# CH32V307WCU6-R0.net
KiCad netlist of a schematic drawn in Altium Designer
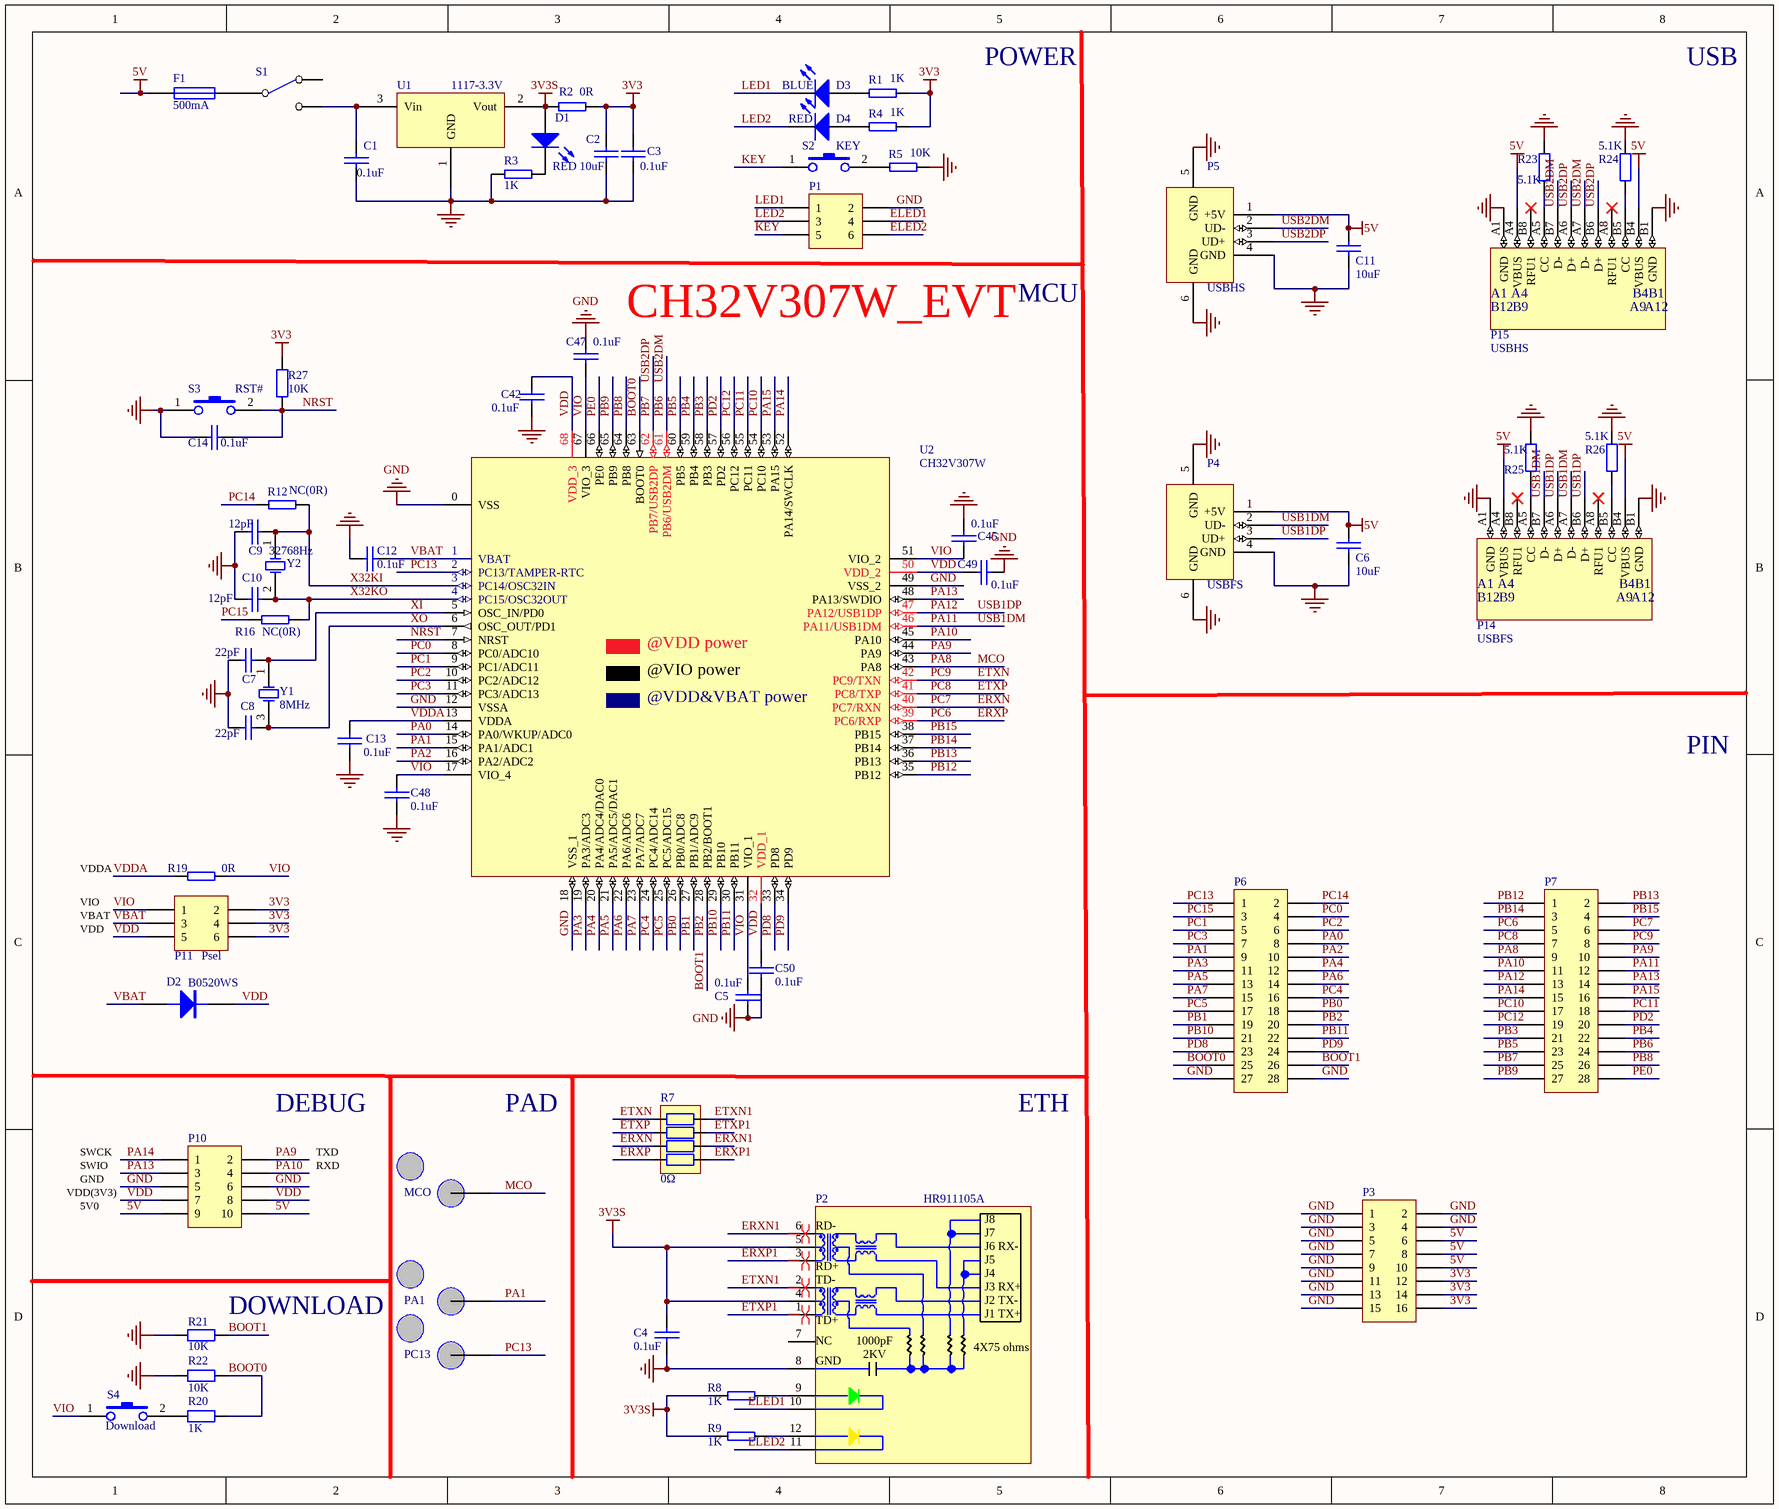
[diagram p0: CH32V307WCU6-R0.SchDoc]

(export (version "E")
  (design (tool "Eeschema 10.0.6"))
  (components
    (comp (ref "C1")
      (value "0.1uF")
      (footprint "0603_C")
      (description "Capacitor")
      (libsource (lib "*") (part "CAP"))
    )
    (comp (ref "C2")
      (value "10uF")
      (footprint "3216_C")
      (description "Capacitor")
      (libsource (lib "*") (part "CAP"))
    )
    (comp (ref "C3")
      (value "0.1uF")
      (footprint "0603_C")
      (description "Capacitor")
      (libsource (lib "*") (part "CAP"))
    )
    (comp (ref "C4")
      (value "0.1uF")
      (footprint "0603_C")
      (description "Capacitor")
      (libsource (lib "*") (part "CAP"))
    )
    (comp (ref "C5")
      (value "0.1uF")
      (footprint "0603_C")
      (description "Capacitor")
      (libsource (lib "*") (part "CAP"))
    )
    (comp (ref "C6")
      (value "10uF")
      (footprint "3216_C")
      (description "Capacitor")
      (libsource (lib "") (part "CAP_1"))
    )
    (comp (ref "C7")
      (value "22pF")
      (footprint "0603_C")
      (description "Capacitor")
      (libsource (lib "*") (part "CAP"))
    )
    (comp (ref "C8")
      (value "22pF")
      (footprint "0603_C")
      (description "Capacitor")
      (libsource (lib "*") (part "CAP"))
    )
    (comp (ref "C9")
      (value "12pF")
      (footprint "0603_C")
      (description "Capacitor")
      (libsource (lib "*") (part "CAP"))
    )
    (comp (ref "C10")
      (value "12pF")
      (footprint "0603_C")
      (description "Capacitor")
      (libsource (lib "*") (part "CAP"))
    )
    (comp (ref "C11")
      (value "10uF")
      (footprint "3216_C")
      (description "Capacitor")
      (libsource (lib "") (part "CAP_1"))
    )
    (comp (ref "C12")
      (value "0.1uF")
      (footprint "0603_C")
      (description "Capacitor")
      (libsource (lib "*") (part "CAP"))
    )
    (comp (ref "C13")
      (value "0.1uF")
      (footprint "0603_C")
      (description "Capacitor")
      (libsource (lib "*") (part "CAP"))
    )
    (comp (ref "C14")
      (value "0.1uF")
      (footprint "0603_C")
      (description "Capacitor")
      (libsource (lib "") (part "CAP_1"))
    )
    (comp (ref "C42")
      (value "0.1uF")
      (footprint "0603_C")
      (description "Capacitor")
      (libsource (lib "*") (part "CAP"))
    )
    (comp (ref "C45")
      (value "0.1uF")
      (footprint "0603_C")
      (description "Capacitor")
      (libsource (lib "*") (part "CAP"))
    )
    (comp (ref "C47")
      (value "0.1uF")
      (footprint "0603_C")
      (description "Capacitor")
      (libsource (lib "*") (part "CAP"))
    )
    (comp (ref "C48")
      (value "0.1uF")
      (footprint "0603_C")
      (description "Capacitor")
      (libsource (lib "*") (part "CAP"))
    )
    (comp (ref "C49")
      (value "0.1uF")
      (footprint "0603_C")
      (description "Capacitor")
      (libsource (lib "*") (part "CAP"))
    )
    (comp (ref "C50")
      (value "0.1uF")
      (footprint "0603_C")
      (description "Capacitor")
      (libsource (lib "*") (part "CAP"))
    )
    (comp (ref "D1")
      (value "RED")
      (footprint "0603+")
      (description "Typical INFRARED GaAs LED")
      (fields (field (name "PUBLISHER") "Altium Limited"))
      (libsource (lib "*") (part "LED0"))
    )
    (comp (ref "D2")
      (value "B0520WS")
      (footprint "SOD-323")
      (description "Diode")
      (libsource (lib "*") (part "DIODE"))
    )
    (comp (ref "D3")
      (value "BLUE")
      (footprint "0603+")
      (description "Typical INFRARED GaAs LED")
      (fields (field (name "PUBLISHER") "Altium Limited"))
      (libsource (lib "*") (part "LED0"))
    )
    (comp (ref "D4")
      (value "RED")
      (footprint "0603+")
      (description "Typical INFRARED GaAs LED")
      (fields (field (name "PUBLISHER") "Altium Limited"))
      (libsource (lib "*") (part "LED0"))
    )
    (comp (ref "F1")
      (value "500mA")
      (footprint "0603")
      (description "Fuse")
      (libsource (lib "wch_sch_others") (part "FUSE1"))
    )
    (comp (ref "MCO")
      (value "Testpoint")
      (footprint "TESTPOINT1")
      (description "测试点")
      (libsource (lib "wch_sch_others") (part "Testpoint"))
    )
    (comp (ref "P1")
      (value "IO")
      (footprint "IDC6-2.54mm")
      (description "Header, 3-Pin, Dual row, Right Angle")
      (fields (field (name "PUBLISHER") "Altium Limited"))
      (libsource (lib "Miscellaneous Connectors") (part "Header 3X2H"))
    )
    (comp (ref "P2") (value "HR911105A") (footprint "HR911105A") (libsource (lib "*") (part "HR911105A")))
    (comp (ref "P3")
      (value "Ppin")
      (footprint "IDC16-2.54mm")
      (description "Header, 8-Pin, Dual row, Right Angle")
      (fields (field (name "PUBLISHER") "Altium Limited"))
      (libsource (lib "Miscellaneous Connectors") (part "Header 8X2H"))
    )
    (comp (ref "P4")
      (value "USBFS")
      (footprint "USBAF")
      (description "USB Port")
      (libsource (lib "*") (part "USB"))
    )
    (comp (ref "P5")
      (value "USBHS")
      (footprint "USBAF")
      (description "USB Port")
      (libsource (lib "*") (part "USB"))
    )
    (comp (ref "P6")
      (value "HEADER 14x2")
      (footprint "MYPCB:IDC28-2.54MM")
      (description "Header, 14-Pin, Dual row")
      (libsource (lib "wch_sch_others") (part "HEADER 14x2"))
    )
    (comp (ref "P7")
      (value "HEADER 14x2")
      (footprint "MYPCB:IDC28-2.54MM")
      (description "Header, 14-Pin, Dual row")
      (libsource (lib "wch_sch_others") (part "HEADER 14x2"))
    )
    (comp (ref "P10")
      (value "LINK")
      (footprint "IDC10-2.54mm")
      (description "Header, 5-Pin, Dual row, Right Angle")
      (fields (field (name "PUBLISHER") "Altium Limited"))
      (libsource (lib "Miscellaneous Connectors") (part "Header 5X2H"))
    )
    (comp (ref "P11")
      (value "Psel")
      (footprint "IDC6-2.54mm")
      (description "Header, 3-Pin, Dual row, Right Angle")
      (fields (field (name "PUBLISHER") "Altium Limited"))
      (libsource (lib "Miscellaneous Connectors") (part "Header 3X2H"))
    )
    (comp (ref "P14")
      (value "USBFS")
      (footprint "TYPE-C-Receptacle-2.0")
      (libsource (lib "*") (part "TYPE-C1"))
    )
    (comp (ref "P15")
      (value "USBHS")
      (footprint "TYPE-C-Receptacle-2.0")
      (libsource (lib "*") (part "TYPE-C1"))
    )
    (comp (ref "PA1")
      (value "Testpoint")
      (footprint "TESTPOINT1")
      (description "测试点")
      (libsource (lib "wch_sch_others") (part "Testpoint"))
    )
    (comp (ref "PC13")
      (value "Testpoint")
      (footprint "TESTPOINT1")
      (description "测试点")
      (libsource (lib "wch_sch_others") (part "Testpoint"))
    )
    (comp (ref "R1") (value "1K") (footprint "0603") (libsource (lib "wch_sch_others") (part "RES")))
    (comp (ref "R2") (value "0R") (footprint "0603") (libsource (lib "wch_sch_others") (part "RES")))
    (comp (ref "R3") (value "1K") (footprint "0603") (libsource (lib "wch_sch_others") (part "RES")))
    (comp (ref "R4") (value "1K") (footprint "0603") (libsource (lib "wch_sch_others") (part "RES")))
    (comp (ref "R5") (value "10K") (footprint "0603") (libsource (lib "wch_sch_others") (part "RES")))
    (comp (ref "R7")
      (value "0Ω")
      (footprint "8P4R-0603")
      (description "贴片网络排阻")
      (fields (field (name "版权归属") "源创客"))
      (libsource (lib "wch_sch_others") (part "R-8P4R"))
    )
    (comp (ref "R8") (value "1K") (footprint "0603") (libsource (lib "wch_sch_others") (part "RES")))
    (comp (ref "R9") (value "1K") (footprint "0603") (libsource (lib "wch_sch_others") (part "RES")))
    (comp (ref "R12") (value "NC(0R)") (footprint "0603") (libsource (lib "wch_sch_others") (part "RES")))
    (comp (ref "R16") (value "NC(0R)") (footprint "0603") (libsource (lib "wch_sch_others") (part "RES")))
    (comp (ref "R19") (value "0R") (footprint "0603") (libsource (lib "*") (part "R")))
    (comp (ref "R20")
      (value "1K")
      (footprint "0603")
      (description "Resistor")
      (fields (field (name "PUBLISHER") "Altium Limited"))
      (libsource (lib "") (part "Res2_1"))
    )
    (comp (ref "R21")
      (value "10K")
      (footprint "0603")
      (description "Resistor")
      (fields (field (name "PUBLISHER") "Altium Limited"))
      (libsource (lib "") (part "Res2_1"))
    )
    (comp (ref "R22")
      (value "10K")
      (footprint "0603")
      (description "Resistor")
      (fields (field (name "PUBLISHER") "Altium Limited"))
      (libsource (lib "") (part "Res2_1"))
    )
    (comp (ref "R23")
      (value "5.1K")
      (footprint "0603")
      (description "Resistor")
      (libsource (lib "Miscellaneous Devices") (part "Res2"))
    )
    (comp (ref "R24")
      (value "5.1K")
      (footprint "0603")
      (description "Resistor")
      (libsource (lib "Miscellaneous Devices") (part "Res2"))
    )
    (comp (ref "R25")
      (value "5.1K")
      (footprint "0603")
      (description "Resistor")
      (libsource (lib "Miscellaneous Devices") (part "Res2"))
    )
    (comp (ref "R26")
      (value "5.1K")
      (footprint "0603")
      (description "Resistor")
      (libsource (lib "Miscellaneous Devices") (part "Res2"))
    )
    (comp (ref "R27")
      (value "10K")
      (footprint "0603")
      (description "Resistor")
      (fields (field (name "PUBLISHER") "Altium Limited"))
      (libsource (lib "Miscellaneous Devices") (part "Res2"))
    )
    (comp (ref "S1") (value "SW SPDT") (footprint "KEY2") (libsource (lib "*") (part "SW SPDT")))
    (comp (ref "S2")
      (value "KEY")
      (footprint "SMD_6.1x3.65x2.5mm-KEY")
      (libsource (lib "wch_sch_others") (part "KEY1"))
    )
    (comp (ref "S3")
      (value "RST#")
      (footprint "SMD_6.1x3.65x2.5mm-KEY")
      (libsource (lib "wch_sch_others") (part "KEY1"))
    )
    (comp (ref "S4")
      (value "Download")
      (footprint "SMD_6.1x3.65x2.5mm-KEY")
      (libsource (lib "wch_sch_others") (part "KEY1"))
    )
    (comp (ref "U1")
      (value "1117-3.3V")
      (footprint "SOT-223")
      (libsource (lib "wch_sch_others") (part "1117-3.3V"))
    )
    (comp (ref "U2")
      (value "CH32V307W")
      (footprint "QFN68_8x8")
      (description "RISC-V FPU HD-MCU, 144MHz, USB_480M, USB OTG, 1000M Ethernet MAC, 2*CAN")
      (libsource (lib "CHXXX") (part "CH32V307W"))
    )
    (comp (ref "Y1")
      (value "8MHz")
      (footprint "XT3225")
      (description "Crystal Oscillator")
      (fields (field (name "PUBLISHER") "Altium Limited"))
      (libsource (lib "") (part "XTAL_1"))
    )
    (comp (ref "Y2")
      (value "32768Hz")
      (footprint "FC-135")
      (description "Crystal Oscillator")
      (fields (field (name "PUBLISHER") "Altium Limited"))
      (libsource (lib "*") (part "XTAL"))
    )
  )
  (nets
    (net (code "2") (name "/BOOT0") (class "Default")
      (node (ref "P6") (pin "25") (pinfunction "25_25") (pintype "passive"))
      (node (ref "R20") (pin "1") (pinfunction "1_1") (pintype "passive"))
      (node (ref "R22") (pin "1") (pinfunction "1_1") (pintype "passive"))
      (node (ref "U2") (pin "63") (pinfunction "BOOT0_63") (pintype "input"))
    )
    (net (code "3") (name "/BOOT1") (class "Default")
      (node (ref "P6") (pin "20") (pinfunction "20_20") (pintype "passive"))
      (node (ref "P6") (pin "26") (pinfunction "26_26") (pintype "passive"))
      (node (ref "R21") (pin "1") (pinfunction "1_1") (pintype "passive"))
      (node (ref "U2") (pin "28") (pinfunction "PB2/BOOT1_28") (pintype "bidirectional"))
    )
    (net (code "4") (name "/ELED1") (class "Default")
      (node (ref "P1") (pin "4") (pinfunction "4_4") (pintype "passive"))
      (node (ref "P2") (pin "10") (pintype "passive"))
    )
    (net (code "5") (name "/ELED2") (class "Default")
      (node (ref "P1") (pin "6") (pinfunction "6_6") (pintype "passive"))
      (node (ref "P2") (pin "11") (pintype "passive"))
    )
    (net (code "6") (name "/ERXN") (class "Default")
      (node (ref "P7") (pin "6") (pinfunction "6_6") (pintype "passive"))
      (node (ref "R7") (pin "3") (pinfunction "3_3") (pintype "passive"))
      (node (ref "U2") (pin "40") (pinfunction "PC7/RXN_40") (pintype "bidirectional"))
    )
    (net (code "7") (name "/ERXN1") (class "Default")
      (node (ref "P2") (pin "6") (pintype "passive"))
      (node (ref "R7") (pin "6") (pinfunction "6_6") (pintype "passive"))
    )
    (net (code "8") (name "/ERXP") (class "Default")
      (node (ref "P7") (pin "5") (pinfunction "5_5") (pintype "passive"))
      (node (ref "R7") (pin "4") (pinfunction "4_4") (pintype "passive"))
      (node (ref "U2") (pin "39") (pinfunction "PC6/RXP_39") (pintype "bidirectional"))
    )
    (net (code "9") (name "/ERXP1") (class "Default")
      (node (ref "P2") (pin "3") (pintype "passive"))
      (node (ref "R7") (pin "5") (pinfunction "5_5") (pintype "passive"))
    )
    (net (code "10") (name "/ETXN") (class "Default")
      (node (ref "P7") (pin "8") (pinfunction "8_8") (pintype "passive"))
      (node (ref "R7") (pin "1") (pinfunction "1_1") (pintype "passive"))
      (node (ref "U2") (pin "42") (pinfunction "PC9/TXN_42") (pintype "bidirectional"))
    )
    (net (code "11") (name "/ETXN1") (class "Default")
      (node (ref "P2") (pin "2") (pintype "passive"))
      (node (ref "R7") (pin "8") (pinfunction "8_8") (pintype "passive"))
    )
    (net (code "12") (name "/ETXP") (class "Default")
      (node (ref "P7") (pin "7") (pinfunction "7_7") (pintype "passive"))
      (node (ref "R7") (pin "2") (pinfunction "2_2") (pintype "passive"))
      (node (ref "U2") (pin "41") (pinfunction "PC8/TXP_41") (pintype "bidirectional"))
    )
    (net (code "13") (name "/ETXP1") (class "Default")
      (node (ref "P2") (pin "1") (pintype "passive"))
      (node (ref "R7") (pin "7") (pinfunction "7_7") (pintype "passive"))
    )
    (net (code "14") (name "/KEY") (class "Default")
      (node (ref "P1") (pin "5") (pinfunction "5_5") (pintype "passive"))
      (node (ref "S2") (pin "1") (pinfunction "1_1") (pintype "passive"))
    )
    (net (code "15") (name "/LED1") (class "Default")
      (node (ref "D3") (pin "2") (pinfunction "K_2") (pintype "passive"))
      (node (ref "P1") (pin "1") (pinfunction "1_1") (pintype "passive"))
    )
    (net (code "16") (name "/LED2") (class "Default")
      (node (ref "D4") (pin "2") (pinfunction "K_2") (pintype "passive"))
      (node (ref "P1") (pin "3") (pinfunction "3_3") (pintype "passive"))
    )
    (net (code "17") (name "/MCO") (class "Default")
      (node (ref "MCO") (pin "1") (pinfunction "point_1") (pintype "passive"))
      (node (ref "P7") (pin "9") (pinfunction "9_9") (pintype "passive"))
      (node (ref "U2") (pin "43") (pinfunction "PA8_43") (pintype "bidirectional"))
    )
    (net (code "18") (name "/NRST") (class "Default")
      (node (ref "C14") (pin "2") (pinfunction "2_2") (pintype "passive"))
      (node (ref "R27") (pin "1") (pinfunction "1_1") (pintype "passive"))
      (node (ref "S3") (pin "2") (pinfunction "2_2") (pintype "passive"))
      (node (ref "U2") (pin "7") (pinfunction "NRST_7") (pintype "input"))
    )
    (net (code "19") (name "/PA0") (class "Default")
      (node (ref "P6") (pin "8") (pinfunction "8_8") (pintype "passive"))
      (node (ref "U2") (pin "14") (pinfunction "PA0/WKUP/ADC0_14") (pintype "bidirectional"))
    )
    (net (code "20") (name "/PA1") (class "Default")
      (node (ref "P6") (pin "9") (pinfunction "9_9") (pintype "passive"))
      (node (ref "PA1") (pin "1") (pinfunction "point_1") (pintype "passive"))
      (node (ref "U2") (pin "15") (pinfunction "PA1/ADC1_15") (pintype "bidirectional"))
    )
    (net (code "21") (name "/PA2") (class "Default")
      (node (ref "P6") (pin "10") (pinfunction "10_10") (pintype "passive"))
      (node (ref "U2") (pin "16") (pinfunction "PA2/ADC2_16") (pintype "bidirectional"))
    )
    (net (code "22") (name "/PA3") (class "Default")
      (node (ref "P6") (pin "11") (pinfunction "11_11") (pintype "passive"))
      (node (ref "U2") (pin "19") (pinfunction "PA3/ADC3_19") (pintype "bidirectional"))
    )
    (net (code "23") (name "/PA4") (class "Default")
      (node (ref "P6") (pin "12") (pinfunction "12_12") (pintype "passive"))
      (node (ref "U2") (pin "20") (pinfunction "PA4/ADC4/DAC0_20") (pintype "bidirectional"))
    )
    (net (code "24") (name "/PA5") (class "Default")
      (node (ref "P6") (pin "13") (pinfunction "13_13") (pintype "passive"))
      (node (ref "U2") (pin "21") (pinfunction "PA5/ADC5/DAC1_21") (pintype "bidirectional"))
    )
    (net (code "25") (name "/PA6") (class "Default")
      (node (ref "P6") (pin "14") (pinfunction "14_14") (pintype "passive"))
      (node (ref "U2") (pin "22") (pinfunction "PA6/ADC6_22") (pintype "bidirectional"))
    )
    (net (code "26") (name "/PA7") (class "Default")
      (node (ref "P6") (pin "15") (pinfunction "15_15") (pintype "passive"))
      (node (ref "U2") (pin "23") (pinfunction "PA7/ADC7_23") (pintype "bidirectional"))
    )
    (net (code "27") (name "/PA9") (class "Default")
      (node (ref "P10") (pin "2") (pinfunction "2_2") (pintype "passive"))
      (node (ref "P7") (pin "10") (pinfunction "10_10") (pintype "passive"))
      (node (ref "U2") (pin "44") (pinfunction "PA9_44") (pintype "bidirectional"))
    )
    (net (code "28") (name "/PA10") (class "Default")
      (node (ref "P10") (pin "4") (pinfunction "4_4") (pintype "passive"))
      (node (ref "P7") (pin "11") (pinfunction "11_11") (pintype "passive"))
      (node (ref "U2") (pin "45") (pinfunction "PA10_45") (pintype "bidirectional"))
    )
    (net (code "29") (name "/PA11") (class "Default")
      (node (ref "P14") (pin "A7") (pinfunction "D-_A7") (pintype "bidirectional"))
      (node (ref "P14") (pin "B7") (pinfunction "D-_B7") (pintype "bidirectional"))
      (node (ref "P4") (pin "2") (pinfunction "UD-_2") (pintype "bidirectional"))
      (node (ref "P7") (pin "12") (pinfunction "12_12") (pintype "passive"))
      (node (ref "U2") (pin "46") (pinfunction "PA11/USB1DM_46") (pintype "bidirectional"))
    )
    (net (code "30") (name "/PA12") (class "Default")
      (node (ref "P14") (pin "A6") (pinfunction "D+_A6") (pintype "bidirectional"))
      (node (ref "P14") (pin "B6") (pinfunction "D+_B6") (pintype "bidirectional"))
      (node (ref "P4") (pin "3") (pinfunction "UD+_3") (pintype "bidirectional"))
      (node (ref "P7") (pin "13") (pinfunction "13_13") (pintype "passive"))
      (node (ref "U2") (pin "47") (pinfunction "PA12/USB1DP_47") (pintype "bidirectional"))
    )
    (net (code "31") (name "/PA13") (class "Default")
      (node (ref "P10") (pin "3") (pinfunction "3_3") (pintype "passive"))
      (node (ref "P7") (pin "14") (pinfunction "14_14") (pintype "passive"))
      (node (ref "U2") (pin "48") (pinfunction "PA13/SWDIO_48") (pintype "bidirectional"))
    )
    (net (code "32") (name "/PA14") (class "Default")
      (node (ref "P10") (pin "1") (pinfunction "1_1") (pintype "passive"))
      (node (ref "P7") (pin "15") (pinfunction "15_15") (pintype "passive"))
      (node (ref "U2") (pin "52") (pinfunction "PA14/SWCLK_52") (pintype "bidirectional"))
    )
    (net (code "33") (name "/PA15") (class "Default")
      (node (ref "P7") (pin "16") (pinfunction "16_16") (pintype "passive"))
      (node (ref "U2") (pin "53") (pinfunction "PA15_53") (pintype "bidirectional"))
    )
    (net (code "34") (name "/PB0") (class "Default")
      (node (ref "P6") (pin "18") (pinfunction "18_18") (pintype "passive"))
      (node (ref "U2") (pin "26") (pinfunction "PB0/ADC8_26") (pintype "bidirectional"))
    )
    (net (code "35") (name "/PB1") (class "Default")
      (node (ref "P6") (pin "19") (pinfunction "19_19") (pintype "passive"))
      (node (ref "U2") (pin "27") (pinfunction "PB1/ADC9_27") (pintype "bidirectional"))
    )
    (net (code "36") (name "/PB3") (class "Default")
      (node (ref "P7") (pin "21") (pinfunction "21_21") (pintype "passive"))
      (node (ref "U2") (pin "58") (pinfunction "PB3_58") (pintype "bidirectional"))
    )
    (net (code "37") (name "/PB4") (class "Default")
      (node (ref "P7") (pin "22") (pinfunction "22_22") (pintype "passive"))
      (node (ref "U2") (pin "59") (pinfunction "PB4_59") (pintype "bidirectional"))
    )
    (net (code "38") (name "/PB5") (class "Default")
      (node (ref "P7") (pin "23") (pinfunction "23_23") (pintype "passive"))
      (node (ref "U2") (pin "60") (pinfunction "PB5_60") (pintype "bidirectional"))
    )
    (net (code "39") (name "/PB6") (class "Default")
      (node (ref "P15") (pin "A7") (pinfunction "D-_A7") (pintype "bidirectional"))
      (node (ref "P15") (pin "B7") (pinfunction "D-_B7") (pintype "bidirectional"))
      (node (ref "P5") (pin "2") (pinfunction "UD-_2") (pintype "bidirectional"))
      (node (ref "P7") (pin "24") (pinfunction "24_24") (pintype "passive"))
      (node (ref "U2") (pin "61") (pinfunction "PB6/USB2DM_61") (pintype "bidirectional"))
    )
    (net (code "40") (name "/PB7") (class "Default")
      (node (ref "P15") (pin "A6") (pinfunction "D+_A6") (pintype "bidirectional"))
      (node (ref "P15") (pin "B6") (pinfunction "D+_B6") (pintype "bidirectional"))
      (node (ref "P5") (pin "3") (pinfunction "UD+_3") (pintype "bidirectional"))
      (node (ref "P7") (pin "25") (pinfunction "25_25") (pintype "passive"))
      (node (ref "U2") (pin "62") (pinfunction "PB7/USB2DP_62") (pintype "bidirectional"))
    )
    (net (code "41") (name "/PB8") (class "Default")
      (node (ref "P7") (pin "26") (pinfunction "26_26") (pintype "passive"))
      (node (ref "U2") (pin "64") (pinfunction "PB8_64") (pintype "bidirectional"))
    )
    (net (code "42") (name "/PB9") (class "Default")
      (node (ref "P7") (pin "27") (pinfunction "27_27") (pintype "passive"))
      (node (ref "U2") (pin "65") (pinfunction "PB9_65") (pintype "bidirectional"))
    )
    (net (code "43") (name "/PB10") (class "Default")
      (node (ref "P6") (pin "21") (pinfunction "21_21") (pintype "passive"))
      (node (ref "U2") (pin "29") (pinfunction "PB10_29") (pintype "bidirectional"))
    )
    (net (code "44") (name "/PB11") (class "Default")
      (node (ref "P6") (pin "22") (pinfunction "22_22") (pintype "passive"))
      (node (ref "U2") (pin "30") (pinfunction "PB11_30") (pintype "bidirectional"))
    )
    (net (code "45") (name "/PB12") (class "Default")
      (node (ref "P7") (pin "1") (pinfunction "1_1") (pintype "passive"))
      (node (ref "U2") (pin "35") (pinfunction "PB12_35") (pintype "bidirectional"))
    )
    (net (code "46") (name "/PB13") (class "Default")
      (node (ref "P7") (pin "2") (pinfunction "2_2") (pintype "passive"))
      (node (ref "U2") (pin "36") (pinfunction "PB13_36") (pintype "bidirectional"))
    )
    (net (code "47") (name "/PB14") (class "Default")
      (node (ref "P7") (pin "3") (pinfunction "3_3") (pintype "passive"))
      (node (ref "U2") (pin "37") (pinfunction "PB14_37") (pintype "bidirectional"))
    )
    (net (code "48") (name "/PB15") (class "Default")
      (node (ref "P7") (pin "4") (pinfunction "4_4") (pintype "passive"))
      (node (ref "U2") (pin "38") (pinfunction "PB15_38") (pintype "bidirectional"))
    )
    (net (code "49") (name "/PC0") (class "Default")
      (node (ref "P6") (pin "4") (pinfunction "4_4") (pintype "passive"))
      (node (ref "U2") (pin "8") (pinfunction "PC0/ADC10_8") (pintype "bidirectional"))
    )
    (net (code "50") (name "/PC1") (class "Default")
      (node (ref "P6") (pin "5") (pinfunction "5_5") (pintype "passive"))
      (node (ref "U2") (pin "9") (pinfunction "PC1/ADC11_9") (pintype "bidirectional"))
    )
    (net (code "51") (name "/PC2") (class "Default")
      (node (ref "P6") (pin "6") (pinfunction "6_6") (pintype "passive"))
      (node (ref "U2") (pin "10") (pinfunction "PC2/ADC12_10") (pintype "bidirectional"))
    )
    (net (code "52") (name "/PC3") (class "Default")
      (node (ref "P6") (pin "7") (pinfunction "7_7") (pintype "passive"))
      (node (ref "U2") (pin "11") (pinfunction "PC3/ADC13_11") (pintype "bidirectional"))
    )
    (net (code "53") (name "/PC4") (class "Default")
      (node (ref "P6") (pin "16") (pinfunction "16_16") (pintype "passive"))
      (node (ref "U2") (pin "24") (pinfunction "PC4/ADC14_24") (pintype "bidirectional"))
    )
    (net (code "54") (name "/PC5") (class "Default")
      (node (ref "P6") (pin "17") (pinfunction "17_17") (pintype "passive"))
      (node (ref "U2") (pin "25") (pinfunction "PC5/ADC15_25") (pintype "bidirectional"))
    )
    (net (code "55") (name "/PC10") (class "Default")
      (node (ref "P7") (pin "17") (pinfunction "17_17") (pintype "passive"))
      (node (ref "U2") (pin "54") (pinfunction "PC10_54") (pintype "bidirectional"))
    )
    (net (code "56") (name "/PC11") (class "Default")
      (node (ref "P7") (pin "18") (pinfunction "18_18") (pintype "passive"))
      (node (ref "U2") (pin "55") (pinfunction "PC11_55") (pintype "bidirectional"))
    )
    (net (code "57") (name "/PC12") (class "Default")
      (node (ref "P7") (pin "19") (pinfunction "19_19") (pintype "passive"))
      (node (ref "U2") (pin "56") (pinfunction "PC12_56") (pintype "bidirectional"))
    )
    (net (code "58") (name "/PC13") (class "Default")
      (node (ref "P6") (pin "1") (pinfunction "1_1") (pintype "passive"))
      (node (ref "PC13") (pin "1") (pinfunction "point_1") (pintype "passive"))
      (node (ref "U2") (pin "2") (pinfunction "PC13/TAMPER-RTC_2") (pintype "bidirectional"))
    )
    (net (code "59") (name "/PC14") (class "Default")
      (node (ref "P6") (pin "2") (pinfunction "2_2") (pintype "passive"))
      (node (ref "R12") (pin "1") (pintype "passive"))
    )
    (net (code "60") (name "/PC15") (class "Default")
      (node (ref "P6") (pin "3") (pinfunction "3_3") (pintype "passive"))
      (node (ref "R16") (pin "1") (pintype "passive"))
    )
    (net (code "61") (name "/PD2") (class "Default")
      (node (ref "P7") (pin "20") (pinfunction "20_20") (pintype "passive"))
      (node (ref "U2") (pin "57") (pinfunction "PD2_57") (pintype "bidirectional"))
    )
    (net (code "62") (name "/PD8") (class "Default")
      (node (ref "P6") (pin "23") (pinfunction "23_23") (pintype "passive"))
      (node (ref "U2") (pin "33") (pinfunction "PD8_33") (pintype "bidirectional"))
    )
    (net (code "63") (name "/PD9") (class "Default")
      (node (ref "P6") (pin "24") (pinfunction "24_24") (pintype "passive"))
      (node (ref "U2") (pin "34") (pinfunction "PD9_34") (pintype "bidirectional"))
    )
    (net (code "64") (name "/PE0") (class "Default")
      (node (ref "P7") (pin "28") (pinfunction "28_28") (pintype "passive"))
      (node (ref "U2") (pin "66") (pinfunction "PE0_66") (pintype "bidirectional"))
    )
    (net (code "65") (name "/VBAT") (class "Default")
      (node (ref "C12") (pin "2") (pinfunction "2_2") (pintype "passive"))
      (node (ref "D2") (pin "1") (pinfunction "A_1") (pintype "passive"))
      (node (ref "P11") (pin "3") (pinfunction "3_3") (pintype "passive"))
      (node (ref "U2") (pin "1") (pinfunction "VBAT_1") (pintype "power_in"))
    )
    (net (code "66") (name "/VDD") (class "Default")
      (node (ref "C42") (pin "2") (pinfunction "2_2") (pintype "passive"))
      (node (ref "C49") (pin "2") (pinfunction "2_2") (pintype "passive"))
      (node (ref "C50") (pin "1") (pinfunction "1_1") (pintype "passive"))
      (node (ref "D2") (pin "2") (pinfunction "K_2") (pintype "passive"))
      (node (ref "P10") (pin "7") (pinfunction "7_7") (pintype "passive"))
      (node (ref "P10") (pin "8") (pinfunction "8_8") (pintype "passive"))
      (node (ref "P11") (pin "5") (pinfunction "5_5") (pintype "passive"))
      (node (ref "U2") (pin "32") (pinfunction "VDD_1_32") (pintype "power_in"))
      (node (ref "U2") (pin "50") (pinfunction "VDD_2_50") (pintype "power_in"))
      (node (ref "U2") (pin "68") (pinfunction "VDD_3_68") (pintype "power_in"))
    )
    (net (code "67") (name "/VDDA") (class "Default")
      (node (ref "C13") (pin "1") (pinfunction "1_1") (pintype "passive"))
      (node (ref "R19") (pin "2") (pinfunction "2_2") (pintype "passive"))
      (node (ref "U2") (pin "13") (pinfunction "VDDA_13") (pintype "power_in"))
    )
    (net (code "68") (name "/VIO") (class "Default")
      (node (ref "C45") (pin "1") (pinfunction "1_1") (pintype "passive"))
      (node (ref "C47") (pin "1") (pinfunction "1_1") (pintype "passive"))
      (node (ref "C48") (pin "1") (pinfunction "1_1") (pintype "passive"))
      (node (ref "C5") (pin "2") (pinfunction "2_2") (pintype "passive"))
      (node (ref "P11") (pin "1") (pinfunction "1_1") (pintype "passive"))
      (node (ref "R19") (pin "1") (pinfunction "1_1") (pintype "passive"))
      (node (ref "S4") (pin "1") (pinfunction "1_1") (pintype "passive"))
      (node (ref "U2") (pin "17") (pinfunction "VIO_4_17") (pintype "power_in"))
      (node (ref "U2") (pin "31") (pinfunction "VIO_1_31") (pintype "power_in"))
      (node (ref "U2") (pin "51") (pinfunction "VIO_2_51") (pintype "power_in"))
      (node (ref "U2") (pin "67") (pinfunction "VIO_3_67") (pintype "power_in"))
    )
    (net (code "69") (name "/X32KI") (class "Default")
      (node (ref "C9") (pin "2") (pinfunction "2_2") (pintype "passive"))
      (node (ref "R12") (pin "2") (pintype "passive"))
      (node (ref "U2") (pin "3") (pinfunction "PC14/OSC32IN_3") (pintype "bidirectional"))
      (node (ref "Y2") (pin "1") (pinfunction "OSC1_1") (pintype "passive"))
    )
    (net (code "70") (name "/X32KO") (class "Default")
      (node (ref "C10") (pin "2") (pinfunction "2_2") (pintype "passive"))
      (node (ref "R16") (pin "2") (pintype "passive"))
      (node (ref "U2") (pin "4") (pinfunction "PC15/OSC32OUT_4") (pintype "bidirectional"))
      (node (ref "Y2") (pin "2") (pinfunction "OSC2_2") (pintype "passive"))
    )
    (net (code "71") (name "/XI") (class "Default")
      (node (ref "C7") (pin "2") (pinfunction "2_2") (pintype "passive"))
      (node (ref "U2") (pin "5") (pinfunction "OSC_IN/PD0_5") (pintype "input"))
      (node (ref "Y1") (pin "1") (pinfunction "OSC1_1") (pintype "passive"))
    )
    (net (code "72") (name "/XO") (class "Default")
      (node (ref "C8") (pin "2") (pinfunction "2_2") (pintype "passive"))
      (node (ref "U2") (pin "6") (pinfunction "OSC_OUT/PD1_6") (pintype "output"))
      (node (ref "Y1") (pin "3") (pinfunction "OSC2_3") (pintype "passive"))
    )
    (net (code "73") (name "3V3") (class "Default")
      (node (ref "C2") (pin "1") (pinfunction "1_1") (pintype "passive"))
      (node (ref "C3") (pin "1") (pinfunction "1_1") (pintype "passive"))
      (node (ref "P11") (pin "2") (pinfunction "2_2") (pintype "passive"))
      (node (ref "P11") (pin "4") (pinfunction "4_4") (pintype "passive"))
      (node (ref "P11") (pin "6") (pinfunction "6_6") (pintype "passive"))
      (node (ref "P3") (pin "12") (pinfunction "12_12") (pintype "passive"))
      (node (ref "P3") (pin "14") (pinfunction "14_14") (pintype "passive"))
      (node (ref "P3") (pin "16") (pinfunction "16_16") (pintype "passive"))
      (node (ref "R1") (pin "1") (pintype "passive"))
      (node (ref "R2") (pin "1") (pintype "passive"))
      (node (ref "R27") (pin "2") (pinfunction "2_2") (pintype "passive"))
      (node (ref "R4") (pin "1") (pintype "passive"))
    )
    (net (code "74") (name "3V3S") (class "Default")
      (node (ref "C4") (pin "2") (pinfunction "2_2") (pintype "passive"))
      (node (ref "D1") (pin "1") (pinfunction "A_1") (pintype "passive"))
      (node (ref "P2") (pin "4") (pintype "passive"))
      (node (ref "P2") (pin "5") (pintype "passive"))
      (node (ref "R2") (pin "2") (pintype "passive"))
      (node (ref "R8") (pin "1") (pintype "passive"))
      (node (ref "R9") (pin "1") (pintype "passive"))
      (node (ref "U1") (pin "2") (pinfunction "Vout_2") (pintype "passive"))
    )
    (net (code "75") (name "5V") (class "Default")
      (node (ref "C11") (pin "1") (pinfunction "1_1") (pintype "passive"))
      (node (ref "C6") (pin "1") (pinfunction "1_1") (pintype "passive"))
      (node (ref "F1") (pin "1") (pinfunction "1_1") (pintype "passive"))
      (node (ref "P10") (pin "10") (pinfunction "10_10") (pintype "passive"))
      (node (ref "P10") (pin "9") (pinfunction "9_9") (pintype "passive"))
      (node (ref "P14") (pin "A4") (pinfunction "VBUS_A4") (pintype "bidirectional"))
      (node (ref "P14") (pin "B4") (pinfunction "VBUS_B4") (pintype "bidirectional"))
      (node (ref "P15") (pin "A4") (pinfunction "VBUS_A4") (pintype "bidirectional"))
      (node (ref "P15") (pin "B4") (pinfunction "VBUS_B4") (pintype "bidirectional"))
      (node (ref "P3") (pin "10") (pinfunction "10_10") (pintype "passive"))
      (node (ref "P3") (pin "6") (pinfunction "6_6") (pintype "passive"))
      (node (ref "P3") (pin "8") (pinfunction "8_8") (pintype "passive"))
      (node (ref "P4") (pin "1") (pinfunction "+5V_1") (pintype "power_in"))
      (node (ref "P5") (pin "1") (pinfunction "+5V_1") (pintype "power_in"))
    )
    (net (code "76") (name "GND") (class "Default")
      (node (ref "C1") (pin "2") (pinfunction "2_2") (pintype "passive"))
      (node (ref "C10") (pin "1") (pinfunction "1_1") (pintype "passive"))
      (node (ref "C11") (pin "2") (pinfunction "2_2") (pintype "passive"))
      (node (ref "C12") (pin "1") (pinfunction "1_1") (pintype "passive"))
      (node (ref "C13") (pin "2") (pinfunction "2_2") (pintype "passive"))
      (node (ref "C14") (pin "1") (pinfunction "1_1") (pintype "passive"))
      (node (ref "C2") (pin "2") (pinfunction "2_2") (pintype "passive"))
      (node (ref "C3") (pin "2") (pinfunction "2_2") (pintype "passive"))
      (node (ref "C4") (pin "1") (pinfunction "1_1") (pintype "passive"))
      (node (ref "C42") (pin "1") (pinfunction "1_1") (pintype "passive"))
      (node (ref "C45") (pin "2") (pinfunction "2_2") (pintype "passive"))
      (node (ref "C47") (pin "2") (pinfunction "2_2") (pintype "passive"))
      (node (ref "C48") (pin "2") (pinfunction "2_2") (pintype "passive"))
      (node (ref "C49") (pin "1") (pinfunction "1_1") (pintype "passive"))
      (node (ref "C5") (pin "1") (pinfunction "1_1") (pintype "passive"))
      (node (ref "C50") (pin "2") (pinfunction "2_2") (pintype "passive"))
      (node (ref "C6") (pin "2") (pinfunction "2_2") (pintype "passive"))
      (node (ref "C7") (pin "1") (pinfunction "1_1") (pintype "passive"))
      (node (ref "C8") (pin "1") (pinfunction "1_1") (pintype "passive"))
      (node (ref "C9") (pin "1") (pinfunction "1_1") (pintype "passive"))
      (node (ref "P1") (pin "2") (pinfunction "2_2") (pintype "passive"))
      (node (ref "P10") (pin "5") (pinfunction "5_5") (pintype "passive"))
      (node (ref "P10") (pin "6") (pinfunction "6_6") (pintype "passive"))
      (node (ref "P14") (pin "A1") (pinfunction "GND_A1") (pintype "bidirectional"))
      (node (ref "P14") (pin "B1") (pinfunction "GND_B1") (pintype "bidirectional"))
      (node (ref "P15") (pin "A1") (pinfunction "GND_A1") (pintype "bidirectional"))
      (node (ref "P15") (pin "B1") (pinfunction "GND_B1") (pintype "bidirectional"))
      (node (ref "P2") (pin "8") (pintype "passive"))
      (node (ref "P3") (pin "1") (pinfunction "1_1") (pintype "passive"))
      (node (ref "P3") (pin "11") (pinfunction "11_11") (pintype "passive"))
      (node (ref "P3") (pin "13") (pinfunction "13_13") (pintype "passive"))
      (node (ref "P3") (pin "15") (pinfunction "15_15") (pintype "passive"))
      (node (ref "P3") (pin "2") (pinfunction "2_2") (pintype "passive"))
      (node (ref "P3") (pin "3") (pinfunction "3_3") (pintype "passive"))
      (node (ref "P3") (pin "4") (pinfunction "4_4") (pintype "passive"))
      (node (ref "P3") (pin "5") (pinfunction "5_5") (pintype "passive"))
      (node (ref "P3") (pin "7") (pinfunction "7_7") (pintype "passive"))
      (node (ref "P3") (pin "9") (pinfunction "9_9") (pintype "passive"))
      (node (ref "P4") (pin "4") (pinfunction "GND_4") (pintype "power_in"))
      (node (ref "P4") (pin "5") (pinfunction "GND_5") (pintype "power_in"))
      (node (ref "P4") (pin "6") (pinfunction "GND_6") (pintype "power_in"))
      (node (ref "P5") (pin "4") (pinfunction "GND_4") (pintype "power_in"))
      (node (ref "P5") (pin "5") (pinfunction "GND_5") (pintype "power_in"))
      (node (ref "P5") (pin "6") (pinfunction "GND_6") (pintype "power_in"))
      (node (ref "P6") (pin "27") (pinfunction "27_27") (pintype "passive"))
      (node (ref "P6") (pin "28") (pinfunction "28_28") (pintype "passive"))
      (node (ref "R21") (pin "2") (pinfunction "2_2") (pintype "passive"))
      (node (ref "R22") (pin "2") (pinfunction "2_2") (pintype "passive"))
      (node (ref "R23") (pin "2") (pinfunction "2_2") (pintype "passive"))
      (node (ref "R24") (pin "2") (pinfunction "2_2") (pintype "passive"))
      (node (ref "R25") (pin "2") (pinfunction "2_2") (pintype "passive"))
      (node (ref "R26") (pin "2") (pinfunction "2_2") (pintype "passive"))
      (node (ref "R3") (pin "2") (pintype "passive"))
      (node (ref "R5") (pin "1") (pintype "passive"))
      (node (ref "S3") (pin "1") (pinfunction "1_1") (pintype "passive"))
      (node (ref "U1") (pin "1") (pinfunction "GND_1") (pintype "passive"))
      (node (ref "U2") (pin "0") (pinfunction "VSS_0") (pintype "power_in"))
      (node (ref "U2") (pin "12") (pinfunction "VSSA_12") (pintype "power_in"))
      (node (ref "U2") (pin "18") (pinfunction "VSS_1_18") (pintype "bidirectional"))
      (node (ref "U2") (pin "49") (pinfunction "VSS_2_49") (pintype "power_in"))
    )
    (net (code "77") (name "Net-(D1-K)") (class "Default")
      (node (ref "D1") (pin "2") (pinfunction "K_2") (pintype "passive"))
      (node (ref "R3") (pin "1") (pintype "passive"))
    )
    (net (code "78") (name "Net-(D3-A)") (class "Default")
      (node (ref "D3") (pin "1") (pinfunction "A_1") (pintype "passive"))
      (node (ref "R1") (pin "2") (pintype "passive"))
    )
    (net (code "79") (name "Net-(D4-A)") (class "Default")
      (node (ref "D4") (pin "1") (pinfunction "A_1") (pintype "passive"))
      (node (ref "R4") (pin "2") (pintype "passive"))
    )
    (net (code "80") (name "Net-(P2-Pad9)") (class "Default")
      (node (ref "P2") (pin "9") (pintype "passive"))
      (node (ref "R8") (pin "2") (pintype "passive"))
    )
    (net (code "81") (name "Net-(P2-Pad12)") (class "Default")
      (node (ref "P2") (pin "12") (pintype "passive"))
      (node (ref "R9") (pin "2") (pintype "passive"))
    )
    (net (code "82") (name "Net-(P14-CC-PadA5)") (class "Default")
      (node (ref "P14") (pin "A5") (pinfunction "CC_A5") (pintype "bidirectional"))
      (node (ref "R25") (pin "1") (pinfunction "1_1") (pintype "passive"))
    )
    (net (code "83") (name "Net-(P14-CC-PadB5)") (class "Default")
      (node (ref "P14") (pin "B5") (pinfunction "CC_B5") (pintype "bidirectional"))
      (node (ref "R26") (pin "1") (pinfunction "1_1") (pintype "passive"))
    )
    (net (code "84") (name "Net-(P15-CC-PadA5)") (class "Default")
      (node (ref "P15") (pin "A5") (pinfunction "CC_A5") (pintype "bidirectional"))
      (node (ref "R23") (pin "1") (pinfunction "1_1") (pintype "passive"))
    )
    (net (code "85") (name "Net-(P15-CC-PadB5)") (class "Default")
      (node (ref "P15") (pin "B5") (pinfunction "CC_B5") (pintype "bidirectional"))
      (node (ref "R24") (pin "1") (pinfunction "1_1") (pintype "passive"))
    )
    (net (code "86") (name "Net-(R5-Pad2)") (class "Default")
      (node (ref "R5") (pin "2") (pintype "passive"))
      (node (ref "S2") (pin "2") (pinfunction "2_2") (pintype "passive"))
    )
    (net (code "87") (name "Net-(R20-Pad2)") (class "Default")
      (node (ref "R20") (pin "2") (pinfunction "2_2") (pintype "passive"))
      (node (ref "S4") (pin "2") (pinfunction "2_2") (pintype "passive"))
    )
    (net (code "88") (name "Net-(S1-COMMON)") (class "Default")
      (node (ref "F1") (pin "2") (pinfunction "2_2") (pintype "passive"))
      (node (ref "S1") (pin "1") (pinfunction "COMMON_1") (pintype "passive"))
    )
    (net (code "89") (name "Net-(S1-NC)") (class "Default")
      (node (ref "C1") (pin "1") (pinfunction "1_1") (pintype "passive"))
      (node (ref "S1") (pin "2") (pinfunction "NC_2") (pintype "passive"))
      (node (ref "U1") (pin "3") (pinfunction "Vin_3") (pintype "passive"))
    )
    (net (code "90") (name "unconnected-(P2-Pad7)") (class "Default")
      (node (ref "P2") (pin "7") (pintype "passive"))
    )
    (net (code "91") (name "unconnected-(P14-RFU1-PadA8)") (class "Default")
      (node (ref "P14") (pin "A8") (pinfunction "RFU1_A8") (pintype "bidirectional+no_connect"))
    )
    (net (code "92") (name "unconnected-(P14-RFU1-PadB8)") (class "Default")
      (node (ref "P14") (pin "B8") (pinfunction "RFU1_B8") (pintype "bidirectional+no_connect"))
    )
    (net (code "93") (name "unconnected-(P15-RFU1-PadA8)") (class "Default")
      (node (ref "P15") (pin "A8") (pinfunction "RFU1_A8") (pintype "bidirectional+no_connect"))
    )
    (net (code "94") (name "unconnected-(P15-RFU1-PadB8)") (class "Default")
      (node (ref "P15") (pin "B8") (pinfunction "RFU1_B8") (pintype "bidirectional+no_connect"))
    )
    (net (code "95") (name "unconnected-(S1-NO-Pad3)") (class "Default")
      (node (ref "S1") (pin "3") (pinfunction "NO_3") (pintype "passive"))
    )
  )
)
